# protecter.net
KiCad netlist of a schematic drawn in Altium Designer
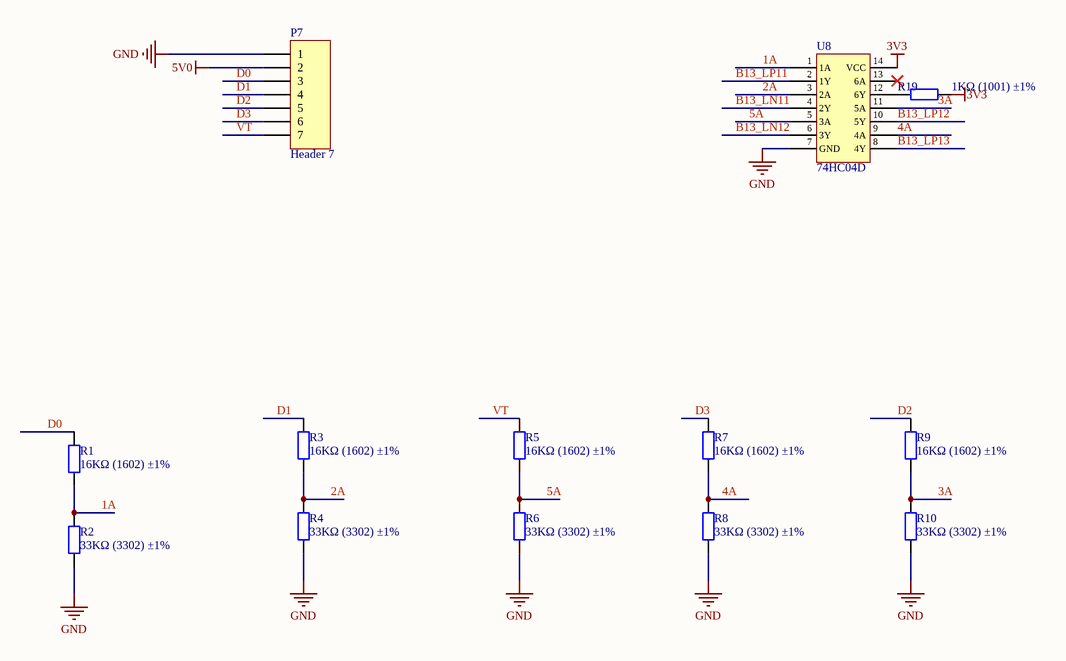
[diagram p0: protecter.SchDoc]

(export (version "E")
  (design (tool "Eeschema 10.0.6"))
  (components
    (comp (ref "P7")
      (value "Header 7")
      (footprint "HDR1X7")
      (description "Header, 7-Pin")
      (fields (field (name "PUBLISHER") "Altium Limited"))
      (libsource (lib "Sparks") (part "Header 7"))
    )
    (comp (ref "R1")
      (value "16KΩ (1602) ±1%")
      (footprint "0603_R")
      (description "贴片电阻")
      (libsource (lib "Miscellaneous Devices LC") (part "0603 16KΩ (1602) 1%"))
    )
    (comp (ref "R2")
      (value "33KΩ (3302) ±1%")
      (footprint "0402_R")
      (description "贴片电阻")
      (libsource (lib "Miscellaneous Devices LC") (part "0402 33KΩ (3302) 1%"))
    )
    (comp (ref "R3")
      (value "16KΩ (1602) ±1%")
      (footprint "0603_R")
      (description "贴片电阻")
      (libsource (lib "Miscellaneous Devices LC") (part "0603 16KΩ (1602) 1%"))
    )
    (comp (ref "R4")
      (value "33KΩ (3302) ±1%")
      (footprint "0402_R")
      (description "贴片电阻")
      (libsource (lib "Miscellaneous Devices LC") (part "0402 33KΩ (3302) 1%"))
    )
    (comp (ref "R5")
      (value "16KΩ (1602) ±1%")
      (footprint "0603_R")
      (description "贴片电阻")
      (libsource (lib "Miscellaneous Devices LC") (part "0603 16KΩ (1602) 1%"))
    )
    (comp (ref "R6")
      (value "33KΩ (3302) ±1%")
      (footprint "0402_R")
      (description "贴片电阻")
      (libsource (lib "Miscellaneous Devices LC") (part "0402 33KΩ (3302) 1%"))
    )
    (comp (ref "R7")
      (value "16KΩ (1602) ±1%")
      (footprint "0603_R")
      (description "贴片电阻")
      (libsource (lib "Miscellaneous Devices LC") (part "0603 16KΩ (1602) 1%"))
    )
    (comp (ref "R8")
      (value "33KΩ (3302) ±1%")
      (footprint "0402_R")
      (description "贴片电阻")
      (libsource (lib "Miscellaneous Devices LC") (part "0402 33KΩ (3302) 1%"))
    )
    (comp (ref "R9")
      (value "16KΩ (1602) ±1%")
      (footprint "0603_R")
      (description "贴片电阻")
      (libsource (lib "Miscellaneous Devices LC") (part "0603 16KΩ (1602) 1%"))
    )
    (comp (ref "R10")
      (value "33KΩ (3302) ±1%")
      (footprint "0402_R")
      (description "贴片电阻")
      (libsource (lib "Miscellaneous Devices LC") (part "0402 33KΩ (3302) 1%"))
    )
    (comp (ref "R19")
      (value "1KΩ (1001) ±1%")
      (footprint "0402_R")
      (description "贴片电阻")
      (libsource (lib "Miscellaneous Devices LC") (part "0402 1KΩ (1001) 1%"))
    )
    (comp (ref "U8")
      (value "74HC04D")
      (footprint "SOIC-14_150mil")
      (libsource (lib "jlcUser") (part "74HC04D"))
    )
  )
  (nets
    (net (code "1") (name "/1A") (class "Default")
      (node (ref "R1") (pin "1") (pinfunction "1_1") (pintype "passive"))
      (node (ref "R2") (pin "2") (pinfunction "2_2") (pintype "passive"))
      (node (ref "U8") (pin "1") (pinfunction "1A_1") (pintype "passive"))
    )
    (net (code "2") (name "/2A") (class "Default")
      (node (ref "R3") (pin "1") (pinfunction "1_1") (pintype "passive"))
      (node (ref "R4") (pin "2") (pinfunction "2_2") (pintype "passive"))
      (node (ref "U8") (pin "3") (pinfunction "2A_3") (pintype "passive"))
    )
    (net (code "3") (name "/3A") (class "Default")
      (node (ref "R10") (pin "2") (pinfunction "2_2") (pintype "passive"))
      (node (ref "R9") (pin "1") (pinfunction "1_1") (pintype "passive"))
      (node (ref "U8") (pin "11") (pinfunction "5A_11") (pintype "passive"))
    )
    (net (code "4") (name "/4A") (class "Default")
      (node (ref "R7") (pin "1") (pinfunction "1_1") (pintype "passive"))
      (node (ref "R8") (pin "2") (pinfunction "2_2") (pintype "passive"))
      (node (ref "U8") (pin "9") (pinfunction "4A_9") (pintype "passive"))
    )
    (net (code "5") (name "/5A") (class "Default")
      (node (ref "R5") (pin "1") (pinfunction "1_1") (pintype "passive"))
      (node (ref "R6") (pin "2") (pinfunction "2_2") (pintype "passive"))
      (node (ref "U8") (pin "5") (pinfunction "3A_5") (pintype "passive"))
    )
    (net (code "6") (name "/B13_LN11") (class "Default")
      (node (ref "U8") (pin "4") (pinfunction "2Y_4") (pintype "passive"))
    )
    (net (code "7") (name "/B13_LN12") (class "Default")
      (node (ref "U8") (pin "6") (pinfunction "3Y_6") (pintype "passive"))
    )
    (net (code "8") (name "/B13_LP11") (class "Default")
      (node (ref "U8") (pin "2") (pinfunction "1Y_2") (pintype "passive"))
    )
    (net (code "9") (name "/B13_LP12") (class "Default")
      (node (ref "U8") (pin "10") (pinfunction "5Y_10") (pintype "passive"))
    )
    (net (code "10") (name "/B13_LP13") (class "Default")
      (node (ref "U8") (pin "8") (pinfunction "4Y_8") (pintype "passive"))
    )
    (net (code "11") (name "/D0") (class "Default")
      (node (ref "P7") (pin "3") (pinfunction "3_3") (pintype "passive"))
      (node (ref "R1") (pin "2") (pinfunction "2_2") (pintype "passive"))
    )
    (net (code "12") (name "/D1") (class "Default")
      (node (ref "P7") (pin "4") (pinfunction "4_4") (pintype "passive"))
      (node (ref "R3") (pin "2") (pinfunction "2_2") (pintype "passive"))
    )
    (net (code "13") (name "/D2") (class "Default")
      (node (ref "P7") (pin "5") (pinfunction "5_5") (pintype "passive"))
      (node (ref "R9") (pin "2") (pinfunction "2_2") (pintype "passive"))
    )
    (net (code "14") (name "/D3") (class "Default")
      (node (ref "P7") (pin "6") (pinfunction "6_6") (pintype "passive"))
      (node (ref "R7") (pin "2") (pinfunction "2_2") (pintype "passive"))
    )
    (net (code "15") (name "/VT") (class "Default")
      (node (ref "P7") (pin "7") (pinfunction "7_7") (pintype "passive"))
      (node (ref "R5") (pin "2") (pinfunction "2_2") (pintype "passive"))
    )
    (net (code "16") (name "3V3") (class "Default")
      (node (ref "R19") (pin "2") (pinfunction "2_2") (pintype "passive"))
      (node (ref "U8") (pin "14") (pinfunction "VCC_14") (pintype "passive"))
    )
    (net (code "17") (name "5V0") (class "Default")
      (node (ref "P7") (pin "2") (pinfunction "2_2") (pintype "passive"))
    )
    (net (code "18") (name "GND") (class "Default")
      (node (ref "P7") (pin "1") (pinfunction "1_1") (pintype "passive"))
      (node (ref "R10") (pin "1") (pinfunction "1_1") (pintype "passive"))
      (node (ref "R2") (pin "1") (pinfunction "1_1") (pintype "passive"))
      (node (ref "R4") (pin "1") (pinfunction "1_1") (pintype "passive"))
      (node (ref "R6") (pin "1") (pinfunction "1_1") (pintype "passive"))
      (node (ref "R8") (pin "1") (pinfunction "1_1") (pintype "passive"))
      (node (ref "U8") (pin "7") (pinfunction "GND_7") (pintype "passive"))
    )
    (net (code "19") (name "Net-(U8-6Y)") (class "Default")
      (node (ref "R19") (pin "1") (pinfunction "1_1") (pintype "passive"))
      (node (ref "U8") (pin "12") (pinfunction "6Y_12") (pintype "passive"))
    )
    (net (code "20") (name "unconnected-(U8-6A-Pad13)") (class "Default")
      (node (ref "U8") (pin "13") (pinfunction "6A_13") (pintype "passive+no_connect"))
    )
  )
)
